# NIRController.net
KiCad netlist of a schematic drawn in Altium Designer
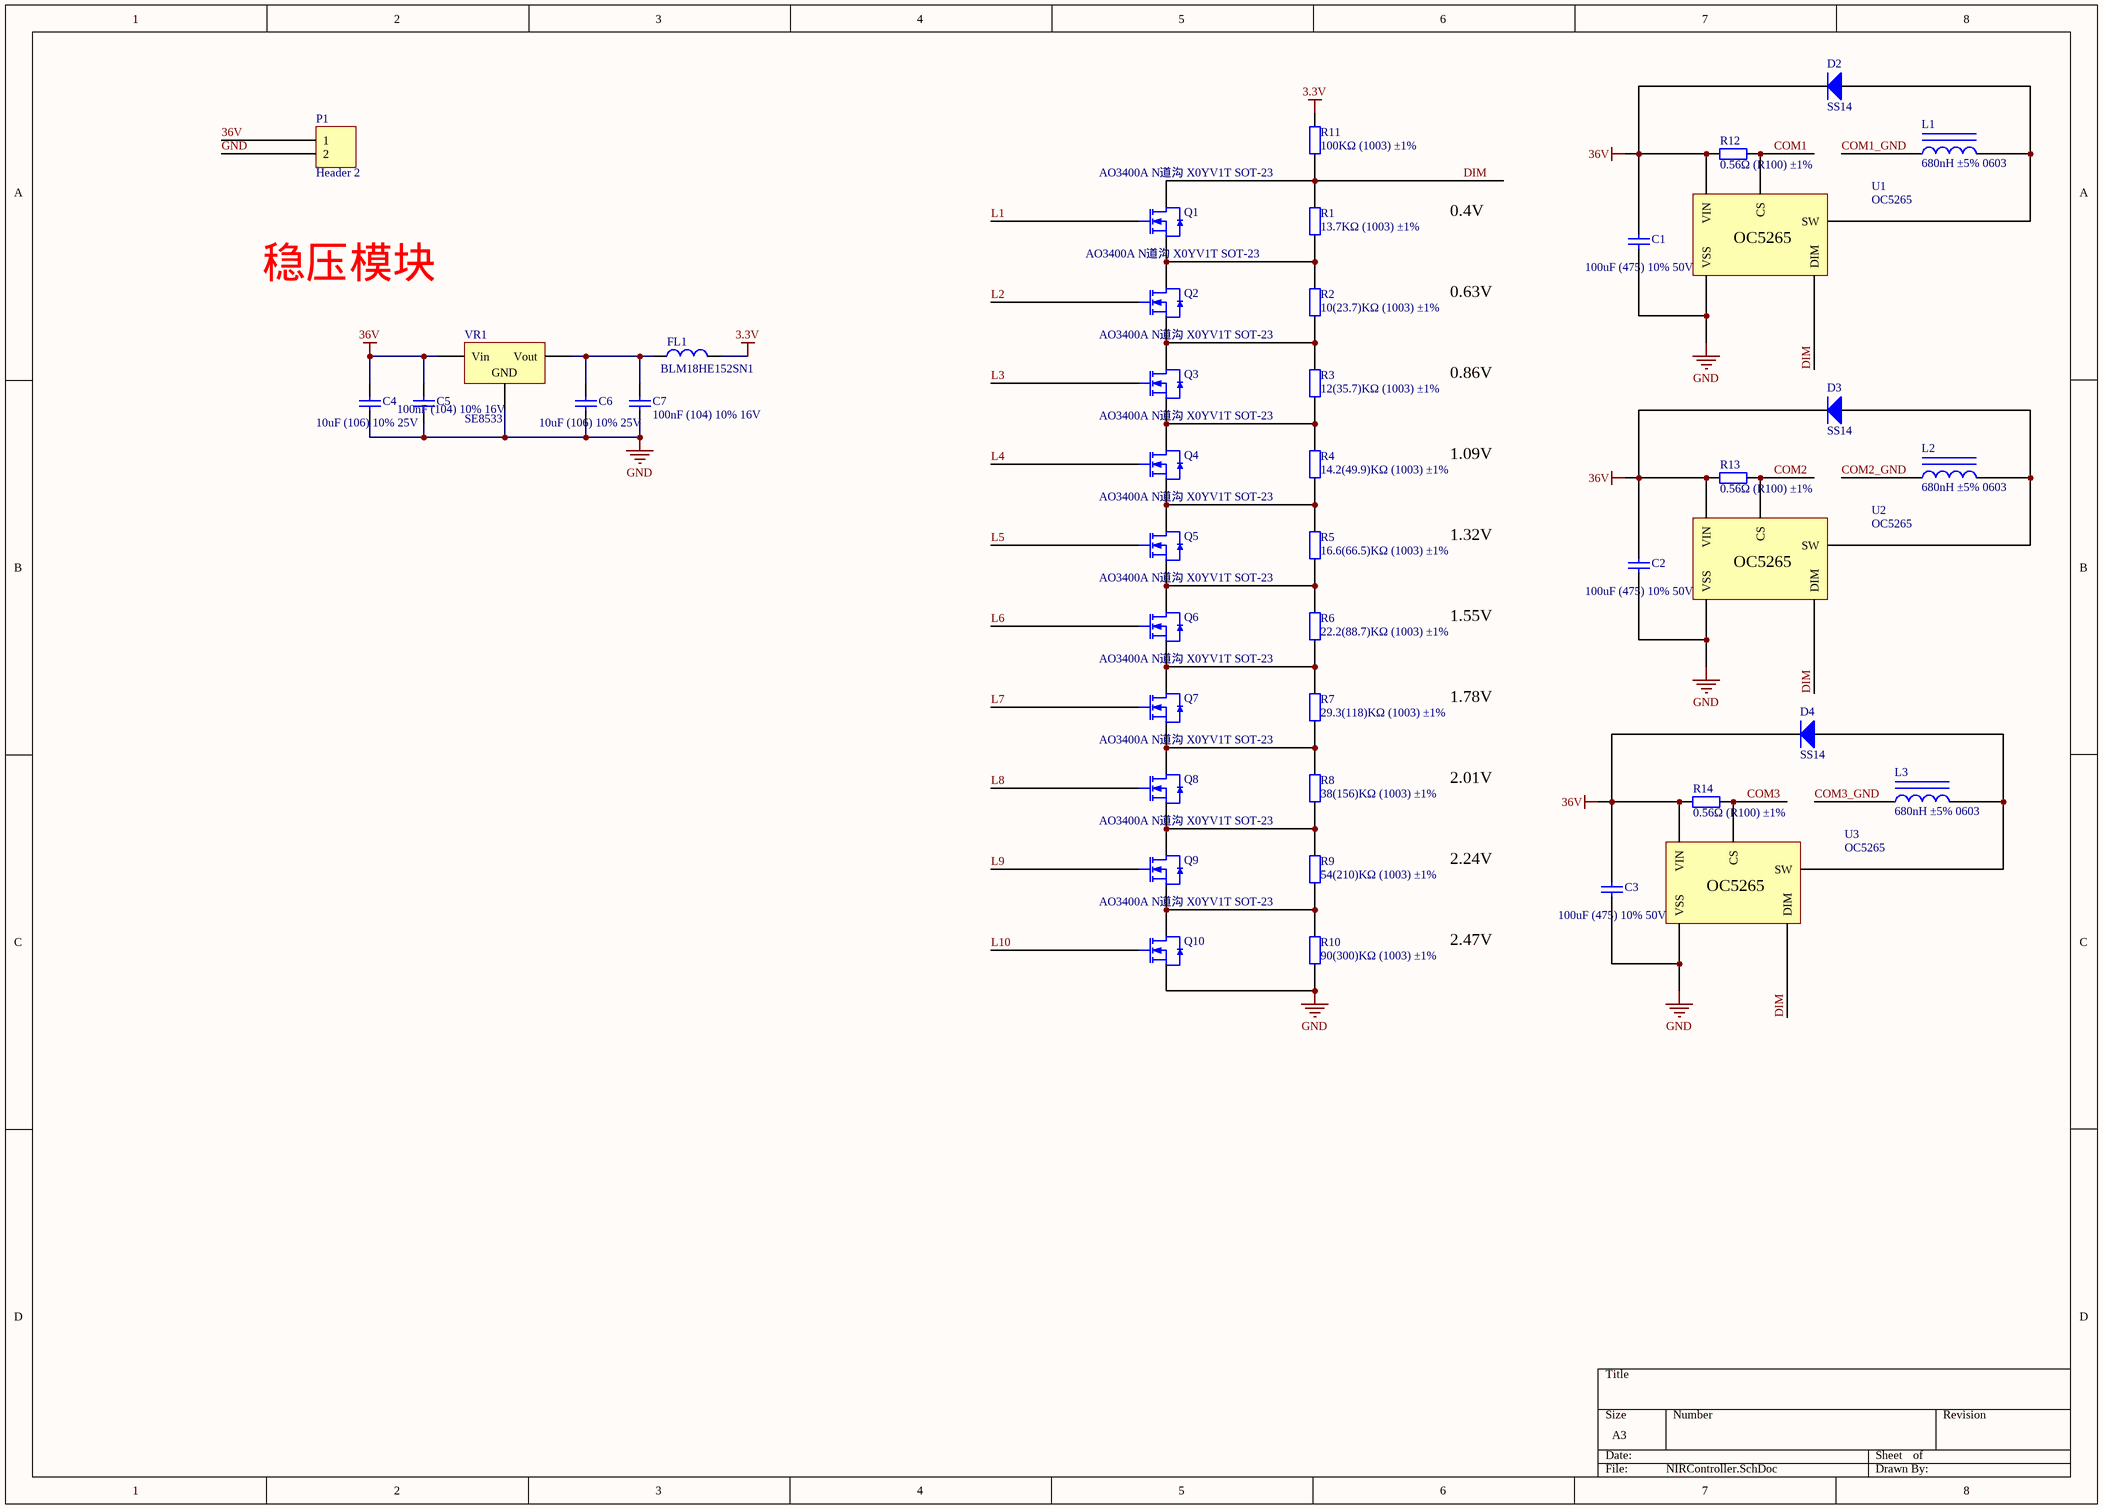
[diagram p0: NIRController.SchDoc]

(export (version "E")
  (design (tool "Eeschema 10.0.6"))
  (components
    (comp (ref "C1")
      (value "100uF (475) 10% 50V")
      (footprint "1206_C")
      (description "贴片电容")
      (libsource (lib "Miscellaneous Devices LC") (part "1206 4.7uF (475) 10% 50V"))
    )
    (comp (ref "C2")
      (value "100uF (475) 10% 50V")
      (footprint "1206_C")
      (description "贴片电容")
      (libsource (lib "Miscellaneous Devices LC") (part "1206 4.7uF (475) 10% 50V"))
    )
    (comp (ref "C3")
      (value "100uF (475) 10% 50V")
      (footprint "1206_C")
      (description "贴片电容")
      (libsource (lib "Miscellaneous Devices LC") (part "1206 4.7uF (475) 10% 50V"))
    )
    (comp (ref "C4")
      (value "10uF (106) 10% 25V")
      (footprint "0603_C")
      (description "贴片电容")
      (libsource (lib "Miscellaneous Devices LC (1)") (part "0805 10uF (106) 10% 25V"))
    )
    (comp (ref "C5")
      (value "100nF (104) 10% 16V")
      (footprint "0603_C")
      (description "贴片电容")
      (libsource (lib "Miscellaneous Devices LC (1)") (part "0402 100nF (104) 10% 16V"))
    )
    (comp (ref "C6")
      (value "10uF (106) 10% 25V")
      (footprint "0603_C")
      (description "贴片电容")
      (libsource (lib "Miscellaneous Devices LC (1)") (part "0805 10uF (106) 10% 25V"))
    )
    (comp (ref "C7")
      (value "100nF (104) 10% 16V")
      (footprint "0603_C")
      (description "贴片电容")
      (libsource (lib "Miscellaneous Devices LC (1)") (part "0402 100nF (104) 10% 16V"))
    )
    (comp (ref "D2")
      (value "SS14")
      (footprint "SMA(DO-214AC)_S1")
      (description "二极管")
      (libsource (lib "Miscellaneous Devices LC") (part "SMA(DO-214AC) SS54"))
    )
    (comp (ref "D3")
      (value "SS14")
      (footprint "SMA(DO-214AC)_S1")
      (description "二极管")
      (libsource (lib "Miscellaneous Devices LC") (part "SMA(DO-214AC) SS54"))
    )
    (comp (ref "D4")
      (value "SS14")
      (footprint "SMA(DO-214AC)_S1")
      (description "二极管")
      (libsource (lib "Miscellaneous Devices LC") (part "SMA(DO-214AC) SS54"))
    )
    (comp (ref "FL1")
      (value "BLM18HE152SN1")
      (footprint "0603_L")
      (description "差模电感1mH/2.5A")
      (libsource (lib "*") (part "IND_DM_1MH_2.5A"))
    )
    (comp (ref "L1")
      (value "680nH ±5% 0603")
      (footprint "0603_L")
      (description "贴片电感")
      (libsource (lib "Miscellaneous Devices LC") (part "0603 68nH 5% 0603"))
    )
    (comp (ref "L2")
      (value "680nH ±5% 0603")
      (footprint "0603_L")
      (description "贴片电感")
      (libsource (lib "Miscellaneous Devices LC") (part "0603 68nH 5% 0603"))
    )
    (comp (ref "L3")
      (value "680nH ±5% 0603")
      (footprint "0603_L")
      (description "贴片电感")
      (libsource (lib "Miscellaneous Devices LC") (part "0603 68nH 5% 0603"))
    )
    (comp (ref "P1")
      (value "Header 2")
      (footprint "HDR1X2")
      (description "Header, 2-Pin")
      (fields (field (name "PUBLISHER") "Altium Limited"))
      (libsource (lib "Miscellaneous Connectors") (part "Header 2"))
    )
    (comp (ref "Q1")
      (value "AO3400A N道沟 X0YV1T SOT-23")
      (footprint "SOT-23-3L")
      (description "MOS(场效应管)")
      (libsource (lib "Miscellaneous Devices LC") (part "AO3400A N道沟 X0YV1T SOT-23"))
    )
    (comp (ref "Q2")
      (value "AO3400A N道沟 X0YV1T SOT-23")
      (footprint "SOT-23-3L")
      (description "MOS(场效应管)")
      (libsource (lib "Miscellaneous Devices LC") (part "AO3400A N道沟 X0YV1T SOT-23"))
    )
    (comp (ref "Q3")
      (value "AO3400A N道沟 X0YV1T SOT-23")
      (footprint "SOT-23-3L")
      (description "MOS(场效应管)")
      (libsource (lib "Miscellaneous Devices LC") (part "AO3400A N道沟 X0YV1T SOT-23"))
    )
    (comp (ref "Q4")
      (value "AO3400A N道沟 X0YV1T SOT-23")
      (footprint "SOT-23-3L")
      (description "MOS(场效应管)")
      (libsource (lib "Miscellaneous Devices LC") (part "AO3400A N道沟 X0YV1T SOT-23"))
    )
    (comp (ref "Q5")
      (value "AO3400A N道沟 X0YV1T SOT-23")
      (footprint "SOT-23-3L")
      (description "MOS(场效应管)")
      (libsource (lib "Miscellaneous Devices LC") (part "AO3400A N道沟 X0YV1T SOT-23"))
    )
    (comp (ref "Q6")
      (value "AO3400A N道沟 X0YV1T SOT-23")
      (footprint "SOT-23-3L")
      (description "MOS(场效应管)")
      (libsource (lib "Miscellaneous Devices LC") (part "AO3400A N道沟 X0YV1T SOT-23"))
    )
    (comp (ref "Q7")
      (value "AO3400A N道沟 X0YV1T SOT-23")
      (footprint "SOT-23-3L")
      (description "MOS(场效应管)")
      (libsource (lib "Miscellaneous Devices LC") (part "AO3400A N道沟 X0YV1T SOT-23"))
    )
    (comp (ref "Q8")
      (value "AO3400A N道沟 X0YV1T SOT-23")
      (footprint "SOT-23-3L")
      (description "MOS(场效应管)")
      (libsource (lib "Miscellaneous Devices LC") (part "AO3400A N道沟 X0YV1T SOT-23"))
    )
    (comp (ref "Q9")
      (value "AO3400A N道沟 X0YV1T SOT-23")
      (footprint "SOT-23-3L")
      (description "MOS(场效应管)")
      (libsource (lib "Miscellaneous Devices LC") (part "AO3400A N道沟 X0YV1T SOT-23"))
    )
    (comp (ref "Q10")
      (value "AO3400A N道沟 X0YV1T SOT-23")
      (footprint "SOT-23-3L")
      (description "MOS(场效应管)")
      (libsource (lib "Miscellaneous Devices LC") (part "AO3400A N道沟 X0YV1T SOT-23"))
    )
    (comp (ref "R1")
      (value "13.7KΩ (1003) ±1%")
      (footprint "0603_R")
      (description "贴片电阻")
      (libsource (lib "Miscellaneous Devices LC") (part "0603 100KΩ (1003) 1%"))
    )
    (comp (ref "R2")
      (value "10(23.7)KΩ (1003) ±1%")
      (footprint "0603_R")
      (description "贴片电阻")
      (libsource (lib "Miscellaneous Devices LC") (part "0603 100KΩ (1003) 1%"))
    )
    (comp (ref "R3")
      (value "12(35.7)KΩ (1003) ±1%")
      (footprint "0603_R")
      (description "贴片电阻")
      (libsource (lib "Miscellaneous Devices LC") (part "0603 100KΩ (1003) 1%"))
    )
    (comp (ref "R4")
      (value "14.2(49.9)KΩ (1003) ±1%")
      (footprint "0603_R")
      (description "贴片电阻")
      (libsource (lib "Miscellaneous Devices LC") (part "0603 100KΩ (1003) 1%"))
    )
    (comp (ref "R5")
      (value "16.6(66.5)KΩ (1003) ±1%")
      (footprint "0603_R")
      (description "贴片电阻")
      (libsource (lib "Miscellaneous Devices LC") (part "0603 100KΩ (1003) 1%"))
    )
    (comp (ref "R6")
      (value "22.2(88.7)KΩ (1003) ±1%")
      (footprint "0603_R")
      (description "贴片电阻")
      (libsource (lib "Miscellaneous Devices LC") (part "0603 100KΩ (1003) 1%"))
    )
    (comp (ref "R7")
      (value "29.3(118)KΩ (1003) ±1%")
      (footprint "0603_R")
      (description "贴片电阻")
      (libsource (lib "Miscellaneous Devices LC") (part "0603 100KΩ (1003) 1%"))
    )
    (comp (ref "R8")
      (value "38(156)KΩ (1003) ±1%")
      (footprint "0603_R")
      (description "贴片电阻")
      (libsource (lib "Miscellaneous Devices LC") (part "0603 100KΩ (1003) 1%"))
    )
    (comp (ref "R9")
      (value "54(210)KΩ (1003) ±1%")
      (footprint "0603_R")
      (description "贴片电阻")
      (libsource (lib "Miscellaneous Devices LC") (part "0603 100KΩ (1003) 1%"))
    )
    (comp (ref "R10")
      (value "90(300)KΩ (1003) ±1%")
      (footprint "0603_R")
      (description "贴片电阻")
      (libsource (lib "Miscellaneous Devices LC") (part "0603 100KΩ (1003) 1%"))
    )
    (comp (ref "R11")
      (value "100KΩ (1003) ±1%")
      (footprint "0603_R")
      (description "贴片电阻")
      (libsource (lib "") (part "0603 100KΩ (1003) 1%_1"))
    )
    (comp (ref "R12")
      (value "0.56Ω (R100) ±1%")
      (footprint "1206_R")
      (description "贴片电阻")
      (libsource (lib "Miscellaneous Devices LC") (part "1206 0.1Ω (R100) 1%"))
    )
    (comp (ref "R13")
      (value "0.56Ω (R100) ±1%")
      (footprint "1206_R")
      (description "贴片电阻")
      (libsource (lib "Miscellaneous Devices LC") (part "1206 0.1Ω (R100) 1%"))
    )
    (comp (ref "R14")
      (value "0.56Ω (R100) ±1%")
      (footprint "1206_R")
      (description "贴片电阻")
      (libsource (lib "Miscellaneous Devices LC") (part "1206 0.1Ω (R100) 1%"))
    )
    (comp (ref "U1") (value "OC5265") (footprint "SOT-89-5") (libsource (lib "Schlib1") (part "OC5265")))
    (comp (ref "U2") (value "OC5265") (footprint "SOT-89-5") (libsource (lib "Schlib1") (part "OC5265")))
    (comp (ref "U3") (value "OC5265") (footprint "SOT-89-5") (libsource (lib "Schlib1") (part "OC5265")))
    (comp (ref "VR1")
      (value "SE8533")
      (footprint "SOT-223")
      (description "低压差线性稳压(LDO)")
      (libsource (lib "Miscellaneous Devices LC") (part "SOT-223 AMS1117-3.3"))
    )
  )
  (nets
    (net (code "1") (name "/COM1") (class "Default")
      (node (ref "R12") (pin "2") (pinfunction "2_2") (pintype "passive"))
      (node (ref "U1") (pin "CS") (pinfunction "CS_CS") (pintype "passive"))
    )
    (net (code "2") (name "/COM1_GND") (class "Default")
      (node (ref "L1") (pin "1") (pinfunction "1_1") (pintype "passive"))
    )
    (net (code "3") (name "/COM2") (class "Default")
      (node (ref "R13") (pin "2") (pinfunction "2_2") (pintype "passive"))
      (node (ref "U2") (pin "CS") (pinfunction "CS_CS") (pintype "passive"))
    )
    (net (code "4") (name "/COM2_GND") (class "Default")
      (node (ref "L2") (pin "1") (pinfunction "1_1") (pintype "passive"))
    )
    (net (code "5") (name "/COM3") (class "Default")
      (node (ref "R14") (pin "2") (pinfunction "2_2") (pintype "passive"))
      (node (ref "U3") (pin "CS") (pinfunction "CS_CS") (pintype "passive"))
    )
    (net (code "6") (name "/COM3_GND") (class "Default")
      (node (ref "L3") (pin "1") (pinfunction "1_1") (pintype "passive"))
    )
    (net (code "7") (name "/DIM") (class "Default")
      (node (ref "Q1") (pin "3") (pinfunction "D_3") (pintype "passive"))
      (node (ref "R1") (pin "2") (pinfunction "2_2") (pintype "passive"))
      (node (ref "R11") (pin "2") (pinfunction "2_2") (pintype "passive"))
      (node (ref "U1") (pin "DIM") (pinfunction "DIM_DIM") (pintype "passive"))
      (node (ref "U2") (pin "DIM") (pinfunction "DIM_DIM") (pintype "passive"))
      (node (ref "U3") (pin "DIM") (pinfunction "DIM_DIM") (pintype "passive"))
    )
    (net (code "8") (name "/L1") (class "Default")
      (node (ref "Q1") (pin "1") (pinfunction "G_1") (pintype "passive"))
    )
    (net (code "9") (name "/L2") (class "Default")
      (node (ref "Q2") (pin "1") (pinfunction "G_1") (pintype "passive"))
    )
    (net (code "10") (name "/L3") (class "Default")
      (node (ref "Q3") (pin "1") (pinfunction "G_1") (pintype "passive"))
    )
    (net (code "11") (name "/L4") (class "Default")
      (node (ref "Q4") (pin "1") (pinfunction "G_1") (pintype "passive"))
    )
    (net (code "12") (name "/L5") (class "Default")
      (node (ref "Q5") (pin "1") (pinfunction "G_1") (pintype "passive"))
    )
    (net (code "13") (name "/L6") (class "Default")
      (node (ref "Q6") (pin "1") (pinfunction "G_1") (pintype "passive"))
    )
    (net (code "14") (name "/L7") (class "Default")
      (node (ref "Q7") (pin "1") (pinfunction "G_1") (pintype "passive"))
    )
    (net (code "15") (name "/L8") (class "Default")
      (node (ref "Q8") (pin "1") (pinfunction "G_1") (pintype "passive"))
    )
    (net (code "16") (name "/L9") (class "Default")
      (node (ref "Q9") (pin "1") (pinfunction "G_1") (pintype "passive"))
    )
    (net (code "17") (name "/L10") (class "Default")
      (node (ref "Q10") (pin "1") (pinfunction "G_1") (pintype "passive"))
    )
    (net (code "18") (name "3.3V") (class "Default")
      (node (ref "FL1") (pin "2") (pinfunction "2_2") (pintype "passive"))
      (node (ref "R11") (pin "1") (pinfunction "1_1") (pintype "passive"))
    )
    (net (code "19") (name "36V") (class "Default")
      (node (ref "C1") (pin "2") (pinfunction "2_2") (pintype "passive"))
      (node (ref "C2") (pin "2") (pinfunction "2_2") (pintype "passive"))
      (node (ref "C3") (pin "2") (pinfunction "2_2") (pintype "passive"))
      (node (ref "C4") (pin "2") (pinfunction "2_2") (pintype "passive"))
      (node (ref "C5") (pin "2") (pinfunction "2_2") (pintype "passive"))
      (node (ref "D2") (pin "2") (pinfunction "K_2") (pintype "passive"))
      (node (ref "D3") (pin "2") (pinfunction "K_2") (pintype "passive"))
      (node (ref "D4") (pin "2") (pinfunction "K_2") (pintype "passive"))
      (node (ref "P1") (pin "1") (pinfunction "1_1") (pintype "passive"))
      (node (ref "R12") (pin "1") (pinfunction "1_1") (pintype "passive"))
      (node (ref "R13") (pin "1") (pinfunction "1_1") (pintype "passive"))
      (node (ref "R14") (pin "1") (pinfunction "1_1") (pintype "passive"))
      (node (ref "U1") (pin "VIN") (pinfunction "VIN_VIN") (pintype "passive"))
      (node (ref "U2") (pin "VIN") (pinfunction "VIN_VIN") (pintype "passive"))
      (node (ref "U3") (pin "VIN") (pinfunction "VIN_VIN") (pintype "passive"))
      (node (ref "VR1") (pin "3") (pinfunction "Vin_3") (pintype "passive"))
    )
    (net (code "20") (name "GND") (class "Default")
      (node (ref "C1") (pin "1") (pinfunction "1_1") (pintype "passive"))
      (node (ref "C2") (pin "1") (pinfunction "1_1") (pintype "passive"))
      (node (ref "C3") (pin "1") (pinfunction "1_1") (pintype "passive"))
      (node (ref "C4") (pin "1") (pinfunction "1_1") (pintype "passive"))
      (node (ref "C5") (pin "1") (pinfunction "1_1") (pintype "passive"))
      (node (ref "C6") (pin "1") (pinfunction "1_1") (pintype "passive"))
      (node (ref "C7") (pin "1") (pinfunction "1_1") (pintype "passive"))
      (node (ref "P1") (pin "2") (pinfunction "2_2") (pintype "passive"))
      (node (ref "Q10") (pin "2") (pinfunction "S_2") (pintype "passive"))
      (node (ref "R10") (pin "1") (pinfunction "1_1") (pintype "passive"))
      (node (ref "U1") (pin "VSS") (pinfunction "VSS_VSS") (pintype "passive"))
      (node (ref "U2") (pin "VSS") (pinfunction "VSS_VSS") (pintype "passive"))
      (node (ref "U3") (pin "VSS") (pinfunction "VSS_VSS") (pintype "passive"))
      (node (ref "VR1") (pin "1") (pinfunction "GND_1") (pintype "passive"))
    )
    (net (code "21") (name "Net-(D2-A)") (class "Default")
      (node (ref "D2") (pin "1") (pinfunction "A_1") (pintype "passive"))
      (node (ref "L1") (pin "2") (pinfunction "2_2") (pintype "passive"))
      (node (ref "U1") (pin "SW") (pinfunction "SW_SW") (pintype "passive"))
    )
    (net (code "22") (name "Net-(D3-A)") (class "Default")
      (node (ref "D3") (pin "1") (pinfunction "A_1") (pintype "passive"))
      (node (ref "L2") (pin "2") (pinfunction "2_2") (pintype "passive"))
      (node (ref "U2") (pin "SW") (pinfunction "SW_SW") (pintype "passive"))
    )
    (net (code "23") (name "Net-(D4-A)") (class "Default")
      (node (ref "D4") (pin "1") (pinfunction "A_1") (pintype "passive"))
      (node (ref "L3") (pin "2") (pinfunction "2_2") (pintype "passive"))
      (node (ref "U3") (pin "SW") (pinfunction "SW_SW") (pintype "passive"))
    )
    (net (code "24") (name "Net-(Q1-S)") (class "Default")
      (node (ref "Q1") (pin "2") (pinfunction "S_2") (pintype "passive"))
      (node (ref "Q2") (pin "3") (pinfunction "D_3") (pintype "passive"))
      (node (ref "R1") (pin "1") (pinfunction "1_1") (pintype "passive"))
      (node (ref "R2") (pin "2") (pinfunction "2_2") (pintype "passive"))
    )
    (net (code "25") (name "Net-(Q2-S)") (class "Default")
      (node (ref "Q2") (pin "2") (pinfunction "S_2") (pintype "passive"))
      (node (ref "Q3") (pin "3") (pinfunction "D_3") (pintype "passive"))
      (node (ref "R2") (pin "1") (pinfunction "1_1") (pintype "passive"))
      (node (ref "R3") (pin "2") (pinfunction "2_2") (pintype "passive"))
    )
    (net (code "26") (name "Net-(Q3-S)") (class "Default")
      (node (ref "Q3") (pin "2") (pinfunction "S_2") (pintype "passive"))
      (node (ref "Q4") (pin "3") (pinfunction "D_3") (pintype "passive"))
      (node (ref "R3") (pin "1") (pinfunction "1_1") (pintype "passive"))
      (node (ref "R4") (pin "2") (pinfunction "2_2") (pintype "passive"))
    )
    (net (code "27") (name "Net-(Q4-S)") (class "Default")
      (node (ref "Q4") (pin "2") (pinfunction "S_2") (pintype "passive"))
      (node (ref "Q5") (pin "3") (pinfunction "D_3") (pintype "passive"))
      (node (ref "R4") (pin "1") (pinfunction "1_1") (pintype "passive"))
      (node (ref "R5") (pin "2") (pinfunction "2_2") (pintype "passive"))
    )
    (net (code "28") (name "Net-(Q5-S)") (class "Default")
      (node (ref "Q5") (pin "2") (pinfunction "S_2") (pintype "passive"))
      (node (ref "Q6") (pin "3") (pinfunction "D_3") (pintype "passive"))
      (node (ref "R5") (pin "1") (pinfunction "1_1") (pintype "passive"))
      (node (ref "R6") (pin "2") (pinfunction "2_2") (pintype "passive"))
    )
    (net (code "29") (name "Net-(Q6-S)") (class "Default")
      (node (ref "Q6") (pin "2") (pinfunction "S_2") (pintype "passive"))
      (node (ref "Q7") (pin "3") (pinfunction "D_3") (pintype "passive"))
      (node (ref "R6") (pin "1") (pinfunction "1_1") (pintype "passive"))
      (node (ref "R7") (pin "2") (pinfunction "2_2") (pintype "passive"))
    )
    (net (code "30") (name "Net-(Q7-S)") (class "Default")
      (node (ref "Q7") (pin "2") (pinfunction "S_2") (pintype "passive"))
      (node (ref "Q8") (pin "3") (pinfunction "D_3") (pintype "passive"))
      (node (ref "R7") (pin "1") (pinfunction "1_1") (pintype "passive"))
      (node (ref "R8") (pin "2") (pinfunction "2_2") (pintype "passive"))
    )
    (net (code "31") (name "Net-(Q8-S)") (class "Default")
      (node (ref "Q8") (pin "2") (pinfunction "S_2") (pintype "passive"))
      (node (ref "Q9") (pin "3") (pinfunction "D_3") (pintype "passive"))
      (node (ref "R8") (pin "1") (pinfunction "1_1") (pintype "passive"))
      (node (ref "R9") (pin "2") (pinfunction "2_2") (pintype "passive"))
    )
    (net (code "32") (name "Net-(Q10-D)") (class "Default")
      (node (ref "Q10") (pin "3") (pinfunction "D_3") (pintype "passive"))
      (node (ref "Q9") (pin "2") (pinfunction "S_2") (pintype "passive"))
      (node (ref "R10") (pin "2") (pinfunction "2_2") (pintype "passive"))
      (node (ref "R9") (pin "1") (pinfunction "1_1") (pintype "passive"))
    )
    (net (code "33") (name "Net-(VR1-Vout)") (class "Default")
      (node (ref "C6") (pin "2") (pinfunction "2_2") (pintype "passive"))
      (node (ref "C7") (pin "2") (pinfunction "2_2") (pintype "passive"))
      (node (ref "FL1") (pin "1") (pinfunction "1_1") (pintype "passive"))
      (node (ref "VR1") (pin "2") (pinfunction "Vout_2") (pintype "passive"))
    )
  )
)
